# Kicker_Board.net
KiCad netlist of a schematic drawn in EAGLE
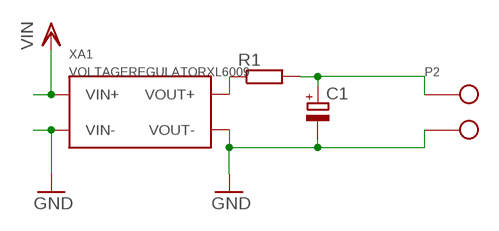
[diagram p0: schematic, sheet 1]

(export (version "E")
  (design (tool "Eeschema 10.0.6"))
  (components
    (comp (ref "C1")
      (value "CPOL-EUE10-35")
      (footprint "eagle-import:EB35D")
      (libsource (lib "eagle-import") (part "CPOL-EUE10-35"))
    )
    (comp (ref "P2")
      (value "TERMINALBLOCK0.15\"")
      (footprint "eagle-import:TERMINALBLOCK0.15_")
      (libsource (lib "eagle-import") (part "TERMINALBLOCK0.15{dblquote}"))
    )
    (comp (ref "R1")
      (value "R-EU_0922/22")
      (footprint "eagle-import:0922_22")
      (libsource (lib "eagle-import") (part "R-EU_0922/22"))
    )
    (comp (ref "XA1")
      (value "VOLTAGEREGULATORXL6009")
      (footprint "eagle-import:XL6009PCB")
      (libsource (lib "eagle-import") (part "VOLTAGEREGULATORXL6009"))
    )
  )
  (nets
    (net (code "1") (name "GND") (class "Default")
      (node (ref "C1") (pin "-") (pinfunction "-_-") (pintype "passive"))
      (node (ref "P2") (pin "P$2") (pinfunction "PIN2_P$2") (pintype "bidirectional"))
      (node (ref "XA1") (pin "IN-") (pinfunction "VIN-_IN-") (pintype "power_in"))
      (node (ref "XA1") (pin "OUT-") (pinfunction "VOUT-_OUT-") (pintype "power_in"))
    )
    (net (code "2") (name "Net-(P2-PIN1)") (class "Default")
      (node (ref "C1") (pin "+") (pinfunction "+_+") (pintype "passive"))
      (node (ref "P2") (pin "P$1") (pinfunction "PIN1_P$1") (pintype "bidirectional"))
      (node (ref "R1") (pin "2") (pinfunction "2_2") (pintype "passive"))
    )
    (net (code "3") (name "Net-(XA1-VOUT+)") (class "Default")
      (node (ref "R1") (pin "1") (pinfunction "1_1") (pintype "passive"))
      (node (ref "XA1") (pin "OUT+") (pinfunction "VOUT+_OUT+") (pintype "power_in"))
    )
    (net (code "4") (name "VIN") (class "Default")
      (node (ref "XA1") (pin "IN+") (pinfunction "VIN+_IN+") (pintype "power_in"))
    )
  )
)
